# v1-eyeballs.net
KiCad netlist of a schematic drawn in EAGLE
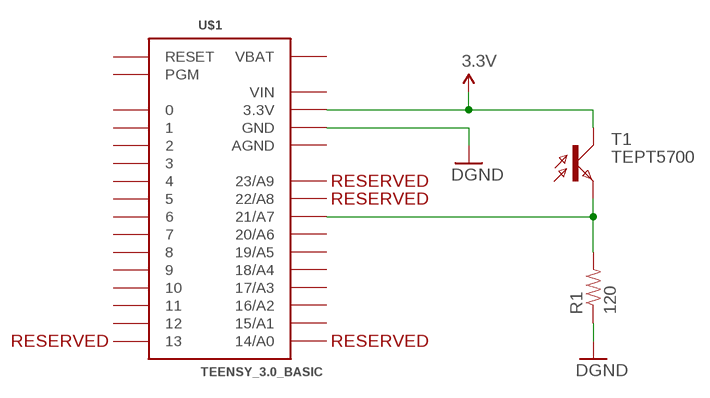
[diagram p0: schematic, sheet 1]

(export (version "E")
  (design (tool "Eeschema 10.0.6"))
  (components
    (comp (ref "R1")
      (value "120")
      (footprint "eagle-import:AXIAL-0.3EZ")
      (libsource (lib "eagle-import") (part "RESISTOREZ"))
    )
    (comp (ref "T1")
      (value "TEPT5700")
      (footprint "eagle-import:BPX81")
      (libsource (lib "eagle-import") (part "BPX81"))
    )
    (comp (ref "U$1")
      (value "TEENSY_3.0_BASIC")
      (footprint "eagle-import:TEENSY_3.0_BASIC")
      (libsource (lib "eagle-import") (part "TEENSY_3.0_BASIC"))
    )
  )
  (nets
    (net (code "1") (name "/AGND") (class "Default")
      (node (ref "U$1") (pin "AGND") (pinfunction "AGND_AGND") (pintype "power_in"))
    )
    (net (code "2") (name "/VBAT") (class "Default")
      (node (ref "U$1") (pin "VBAT") (pinfunction "VBAT_VBAT") (pintype "power_in"))
    )
    (net (code "3") (name "/VIN") (class "Default")
      (node (ref "U$1") (pin "VIN") (pinfunction "VIN_VIN") (pintype "power_in"))
    )
    (net (code "4") (name "3.3V") (class "Default")
      (node (ref "T1") (pin "C") (pinfunction "C_C") (pintype "passive"))
      (node (ref "U$1") (pin "3.3V") (pinfunction "3.3V_3.3V") (pintype "power_in"))
      (node (ref "U$1") (pin "3.3V1") (pinfunction "3.3V_3.3V1") (pintype "power_in"))
    )
    (net (code "5") (name "DGND") (class "Default")
      (node (ref "R1") (pin "P$1") (pinfunction "1_P$1") (pintype "passive"))
      (node (ref "U$1") (pin "GND") (pinfunction "GND_GND") (pintype "power_in"))
      (node (ref "U$1") (pin "GND1") (pinfunction "GND_GND1") (pintype "power_in"))
    )
    (net (code "6") (name "Net-(R1-2)") (class "Default")
      (node (ref "R1") (pin "P$2") (pinfunction "2_P$2") (pintype "passive"))
      (node (ref "T1") (pin "E") (pinfunction "E_E") (pintype "passive"))
      (node (ref "U$1") (pin "21/A7") (pinfunction "21/A7_21/A7") (pintype "bidirectional"))
    )
    (net (code "7") (name "unconnected-(U$1-Pad0)") (class "Default")
      (node (ref "U$1") (pin "0") (pinfunction "0_0") (pintype "bidirectional"))
    )
    (net (code "8") (name "unconnected-(U$1-Pad1)") (class "Default")
      (node (ref "U$1") (pin "1") (pinfunction "1_1") (pintype "bidirectional"))
    )
    (net (code "9") (name "unconnected-(U$1-Pad2)") (class "Default")
      (node (ref "U$1") (pin "2") (pinfunction "2_2") (pintype "bidirectional"))
    )
    (net (code "10") (name "unconnected-(U$1-Pad3)") (class "Default")
      (node (ref "U$1") (pin "3") (pinfunction "3_3") (pintype "bidirectional"))
    )
    (net (code "11") (name "unconnected-(U$1-Pad4)") (class "Default")
      (node (ref "U$1") (pin "4") (pinfunction "4_4") (pintype "bidirectional"))
    )
    (net (code "12") (name "unconnected-(U$1-Pad5)") (class "Default")
      (node (ref "U$1") (pin "5") (pinfunction "5_5") (pintype "bidirectional"))
    )
    (net (code "13") (name "unconnected-(U$1-Pad6)") (class "Default")
      (node (ref "U$1") (pin "6") (pinfunction "6_6") (pintype "bidirectional"))
    )
    (net (code "14") (name "unconnected-(U$1-Pad7)") (class "Default")
      (node (ref "U$1") (pin "7") (pinfunction "7_7") (pintype "bidirectional"))
    )
    (net (code "15") (name "unconnected-(U$1-Pad8)") (class "Default")
      (node (ref "U$1") (pin "8") (pinfunction "8_8") (pintype "bidirectional"))
    )
    (net (code "16") (name "unconnected-(U$1-Pad9)") (class "Default")
      (node (ref "U$1") (pin "9") (pinfunction "9_9") (pintype "bidirectional"))
    )
    (net (code "17") (name "unconnected-(U$1-Pad10)") (class "Default")
      (node (ref "U$1") (pin "10") (pinfunction "10_10") (pintype "bidirectional"))
    )
    (net (code "18") (name "unconnected-(U$1-Pad11)") (class "Default")
      (node (ref "U$1") (pin "11") (pinfunction "11_11") (pintype "bidirectional"))
    )
    (net (code "19") (name "unconnected-(U$1-Pad12)") (class "Default")
      (node (ref "U$1") (pin "12") (pinfunction "12_12") (pintype "bidirectional"))
    )
    (net (code "20") (name "unconnected-(U$1-Pad13)") (class "Default")
      (node (ref "U$1") (pin "13") (pinfunction "13_13") (pintype "bidirectional"))
    )
    (net (code "21") (name "unconnected-(U$1-Pad14{slash}A0)") (class "Default")
      (node (ref "U$1") (pin "14/A0") (pinfunction "14/A0_14/A0") (pintype "bidirectional"))
    )
    (net (code "22") (name "unconnected-(U$1-Pad15{slash}A1)") (class "Default")
      (node (ref "U$1") (pin "15/A1") (pinfunction "15/A1_15/A1") (pintype "bidirectional"))
    )
    (net (code "23") (name "unconnected-(U$1-Pad16{slash}A2)") (class "Default")
      (node (ref "U$1") (pin "16/A2") (pinfunction "16/A2_16/A2") (pintype "bidirectional"))
    )
    (net (code "24") (name "unconnected-(U$1-Pad17{slash}A3)") (class "Default")
      (node (ref "U$1") (pin "17/A3") (pinfunction "17/A3_17/A3") (pintype "bidirectional"))
    )
    (net (code "25") (name "unconnected-(U$1-Pad18{slash}A4)") (class "Default")
      (node (ref "U$1") (pin "18/A4") (pinfunction "18/A4_18/A4") (pintype "bidirectional"))
    )
    (net (code "26") (name "unconnected-(U$1-Pad19{slash}A5)") (class "Default")
      (node (ref "U$1") (pin "19/A5") (pinfunction "19/A5_19/A5") (pintype "bidirectional"))
    )
    (net (code "27") (name "unconnected-(U$1-Pad20{slash}A6)") (class "Default")
      (node (ref "U$1") (pin "20/A6") (pinfunction "20/A6_20/A6") (pintype "bidirectional"))
    )
    (net (code "28") (name "unconnected-(U$1-Pad22{slash}A8)") (class "Default")
      (node (ref "U$1") (pin "22/A8") (pinfunction "22/A8_22/A8") (pintype "bidirectional"))
    )
    (net (code "29") (name "unconnected-(U$1-Pad23{slash}A9)") (class "Default")
      (node (ref "U$1") (pin "23/A9") (pinfunction "23/A9_23/A9") (pintype "bidirectional"))
    )
    (net (code "30") (name "unconnected-(U$1-PadPGM)") (class "Default")
      (node (ref "U$1") (pin "PGM") (pinfunction "PGM_PGM") (pintype "bidirectional"))
    )
    (net (code "31") (name "unconnected-(U$1-PadRESET)") (class "Default")
      (node (ref "U$1") (pin "RESET") (pinfunction "RESET_RESET") (pintype "bidirectional"))
    )
  )
)
